# system_electric_diagram__3.net
KiCad netlist of a schematic drawn in Altium Designer
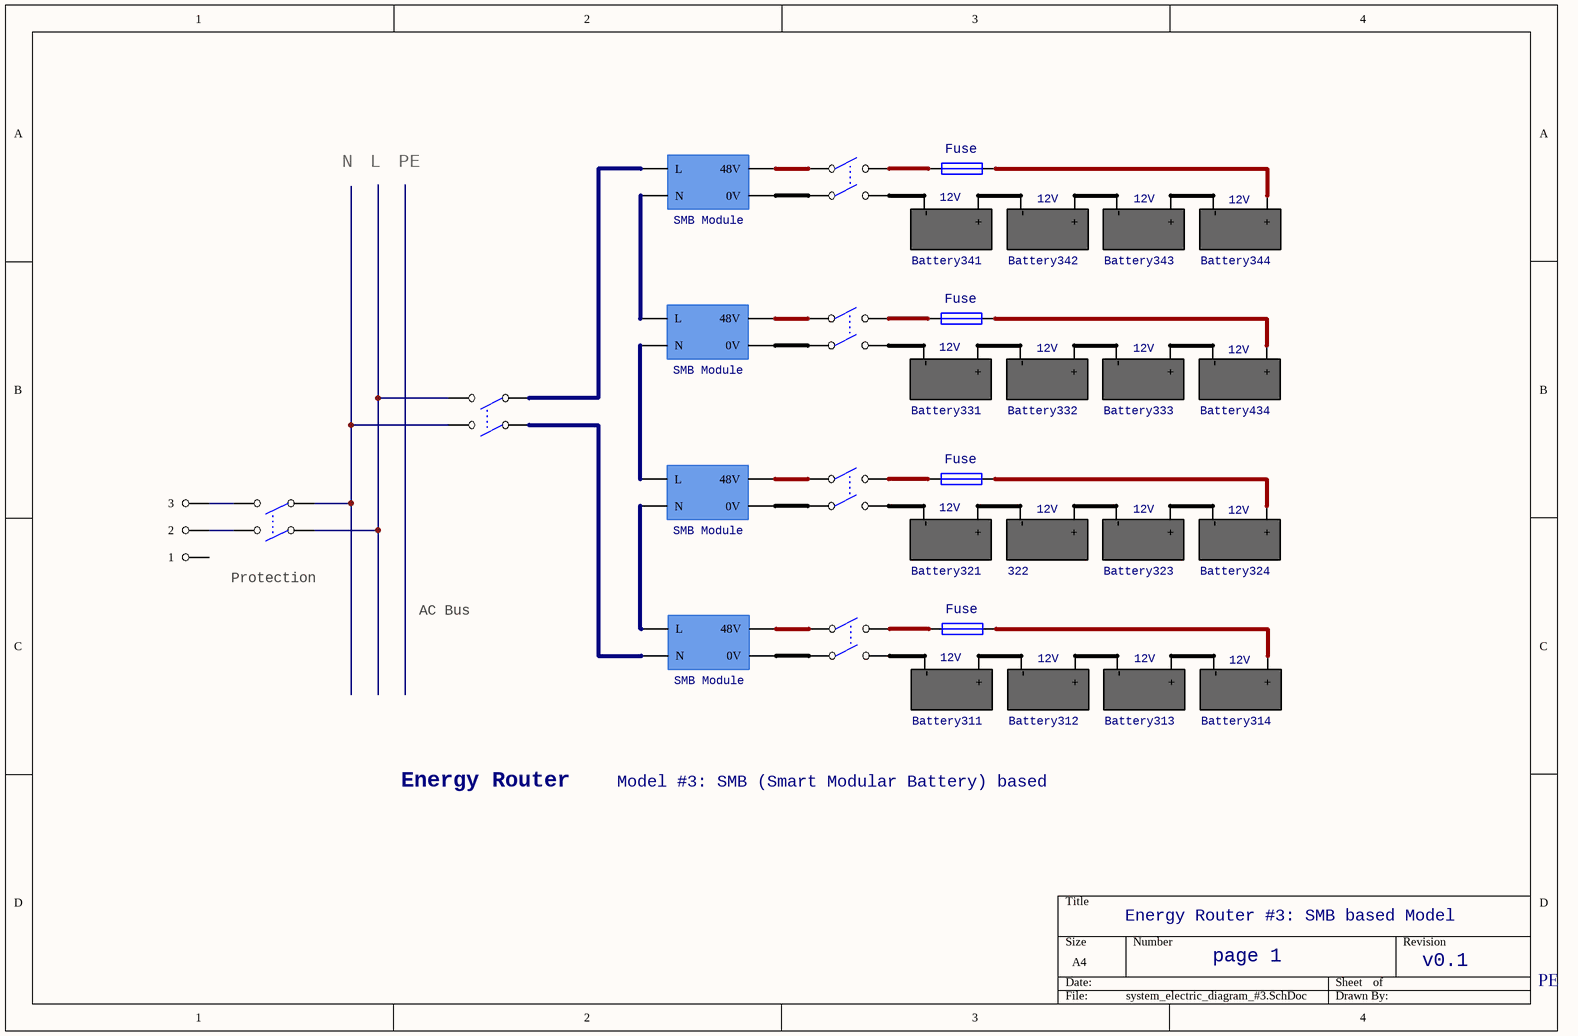
[diagram p0: system_electric_diagram_#3.SchDoc]

(export (version "E")
  (design (tool "Eeschema 10.0.6"))
  (components
    (comp (ref "322") (value "12V") (libsource (lib "0_Schlib-电源柜") (part "1_BAT_12V")))
    (comp (ref "Battery311") (value "12V") (libsource (lib "0_Schlib-电源柜") (part "1_BAT_12V")))
    (comp (ref "Battery312") (value "12V") (libsource (lib "0_Schlib-电源柜") (part "1_BAT_12V")))
    (comp (ref "Battery313") (value "12V") (libsource (lib "0_Schlib-电源柜") (part "1_BAT_12V")))
    (comp (ref "Battery314") (value "12V") (libsource (lib "0_Schlib-电源柜") (part "1_BAT_12V")))
    (comp (ref "Battery321") (value "12V") (libsource (lib "0_Schlib-电源柜") (part "1_BAT_12V")))
    (comp (ref "Battery323") (value "12V") (libsource (lib "0_Schlib-电源柜") (part "1_BAT_12V")))
    (comp (ref "Battery324") (value "12V") (libsource (lib "0_Schlib-电源柜") (part "1_BAT_12V")))
    (comp (ref "Battery331") (value "12V") (libsource (lib "0_Schlib-电源柜") (part "1_BAT_12V")))
    (comp (ref "Battery332") (value "12V") (libsource (lib "0_Schlib-电源柜") (part "1_BAT_12V")))
    (comp (ref "Battery333") (value "12V") (libsource (lib "0_Schlib-电源柜") (part "1_BAT_12V")))
    (comp (ref "Battery341") (value "12V") (libsource (lib "0_Schlib-电源柜") (part "1_BAT_12V")))
    (comp (ref "Battery342") (value "12V") (libsource (lib "0_Schlib-电源柜") (part "1_BAT_12V")))
    (comp (ref "Battery343") (value "12V") (libsource (lib "0_Schlib-电源柜") (part "1_BAT_12V")))
    (comp (ref "Battery344") (value "12V") (libsource (lib "0_Schlib-电源柜") (part "1_BAT_12V")))
    (comp (ref "Battery434") (value "12V") (libsource (lib "0_Schlib-电源柜") (part "1_BAT_12V")))
    (comp (ref "F301") (value "Fuse") (footprint "FUSE1") (libsource (lib "常用元件库") (part "FUSE")))
    (comp (ref "F302") (value "Fuse") (footprint "FUSE1") (libsource (lib "常用元件库") (part "FUSE")))
    (comp (ref "F303") (value "Fuse") (footprint "FUSE1") (libsource (lib "常用元件库") (part "FUSE")))
    (comp (ref "F304") (value "Fuse") (footprint "FUSE1") (libsource (lib "常用元件库") (part "FUSE")))
    (comp (ref "JP301")
      (value "3 HEADER")
      (description "3 Pin Header")
      (libsource (lib "myzou") (part "3 HEADER"))
    )
    (comp (ref "K301") (value "Switch") (libsource (lib "开关") (part "SW-DPST")))
    (comp (ref "K302") (value "Switch") (libsource (lib "开关") (part "SW-DPST")))
    (comp (ref "K303") (value "Switch") (libsource (lib "开关") (part "SW-DPST")))
    (comp (ref "K304") (value "Switch") (libsource (lib "开关") (part "SW-DPST")))
    (comp (ref "K305") (value "Switch") (libsource (lib "开关") (part "SW-DPST")))
    (comp (ref "K306") (value "Switch") (libsource (lib "开关") (part "SW-DPST")))
    (comp (ref "U301") (value "SMB Module") (libsource (lib "Schlib-ORES") (part "20_SMB_Module")))
    (comp (ref "U402") (value "SMB Module") (libsource (lib "Schlib-ORES") (part "20_SMB_Module")))
    (comp (ref "U403") (value "SMB Module") (libsource (lib "Schlib-ORES") (part "20_SMB_Module")))
    (comp (ref "U404") (value "SMB Module") (libsource (lib "Schlib-ORES") (part "20_SMB_Module")))
  )
  (nets
    (net (code "1") (name "Net-(322-+)") (class "Default")
      (node (ref "322") (pin "2") (pinfunction "+_2") (pintype "passive"))
      (node (ref "Battery323") (pin "1") (pinfunction "-_1") (pintype "passive"))
    )
    (net (code "2") (name "Net-(322--)") (class "Default")
      (node (ref "322") (pin "1") (pinfunction "-_1") (pintype "passive"))
      (node (ref "Battery321") (pin "2") (pinfunction "+_2") (pintype "passive"))
    )
    (net (code "3") (name "Net-(Battery311-+)") (class "Default")
      (node (ref "Battery311") (pin "2") (pinfunction "+_2") (pintype "passive"))
      (node (ref "Battery312") (pin "1") (pinfunction "-_1") (pintype "passive"))
    )
    (net (code "4") (name "Net-(Battery311--)") (class "Default")
      (node (ref "Battery311") (pin "1") (pinfunction "-_1") (pintype "passive"))
      (node (ref "K301") (pin "4") (pinfunction "4_4") (pintype "passive"))
    )
    (net (code "5") (name "Net-(Battery312-+)") (class "Default")
      (node (ref "Battery312") (pin "2") (pinfunction "+_2") (pintype "passive"))
      (node (ref "Battery313") (pin "1") (pinfunction "-_1") (pintype "passive"))
    )
    (net (code "6") (name "Net-(Battery313-+)") (class "Default")
      (node (ref "Battery313") (pin "2") (pinfunction "+_2") (pintype "passive"))
      (node (ref "Battery314") (pin "1") (pinfunction "-_1") (pintype "passive"))
    )
    (net (code "7") (name "Net-(Battery314-+)") (class "Default")
      (node (ref "Battery314") (pin "2") (pinfunction "+_2") (pintype "passive"))
      (node (ref "F301") (pin "2") (pinfunction "2_2") (pintype "passive"))
    )
    (net (code "8") (name "Net-(Battery321--)") (class "Default")
      (node (ref "Battery321") (pin "1") (pinfunction "-_1") (pintype "passive"))
      (node (ref "K302") (pin "4") (pinfunction "4_4") (pintype "passive"))
    )
    (net (code "9") (name "Net-(Battery323-+)") (class "Default")
      (node (ref "Battery323") (pin "2") (pinfunction "+_2") (pintype "passive"))
      (node (ref "Battery324") (pin "1") (pinfunction "-_1") (pintype "passive"))
    )
    (net (code "10") (name "Net-(Battery324-+)") (class "Default")
      (node (ref "Battery324") (pin "2") (pinfunction "+_2") (pintype "passive"))
      (node (ref "F302") (pin "2") (pinfunction "2_2") (pintype "passive"))
    )
    (net (code "11") (name "Net-(Battery331-+)") (class "Default")
      (node (ref "Battery331") (pin "2") (pinfunction "+_2") (pintype "passive"))
      (node (ref "Battery332") (pin "1") (pinfunction "-_1") (pintype "passive"))
    )
    (net (code "12") (name "Net-(Battery331--)") (class "Default")
      (node (ref "Battery331") (pin "1") (pinfunction "-_1") (pintype "passive"))
      (node (ref "K303") (pin "4") (pinfunction "4_4") (pintype "passive"))
    )
    (net (code "13") (name "Net-(Battery332-+)") (class "Default")
      (node (ref "Battery332") (pin "2") (pinfunction "+_2") (pintype "passive"))
      (node (ref "Battery333") (pin "1") (pinfunction "-_1") (pintype "passive"))
    )
    (net (code "14") (name "Net-(Battery333-+)") (class "Default")
      (node (ref "Battery333") (pin "2") (pinfunction "+_2") (pintype "passive"))
      (node (ref "Battery434") (pin "1") (pinfunction "-_1") (pintype "passive"))
    )
    (net (code "15") (name "Net-(Battery341-+)") (class "Default")
      (node (ref "Battery341") (pin "2") (pinfunction "+_2") (pintype "passive"))
      (node (ref "Battery342") (pin "1") (pinfunction "-_1") (pintype "passive"))
    )
    (net (code "16") (name "Net-(Battery341--)") (class "Default")
      (node (ref "Battery341") (pin "1") (pinfunction "-_1") (pintype "passive"))
      (node (ref "K304") (pin "4") (pinfunction "4_4") (pintype "passive"))
    )
    (net (code "17") (name "Net-(Battery342-+)") (class "Default")
      (node (ref "Battery342") (pin "2") (pinfunction "+_2") (pintype "passive"))
      (node (ref "Battery343") (pin "1") (pinfunction "-_1") (pintype "passive"))
    )
    (net (code "18") (name "Net-(Battery343-+)") (class "Default")
      (node (ref "Battery343") (pin "2") (pinfunction "+_2") (pintype "passive"))
      (node (ref "Battery344") (pin "1") (pinfunction "-_1") (pintype "passive"))
    )
    (net (code "19") (name "Net-(Battery344-+)") (class "Default")
      (node (ref "Battery344") (pin "2") (pinfunction "+_2") (pintype "passive"))
      (node (ref "F304") (pin "2") (pinfunction "2_2") (pintype "passive"))
    )
    (net (code "20") (name "Net-(Battery434-+)") (class "Default")
      (node (ref "Battery434") (pin "2") (pinfunction "+_2") (pintype "passive"))
      (node (ref "F303") (pin "2") (pinfunction "2_2") (pintype "passive"))
    )
    (net (code "21") (name "Net-(F301-Pad1)") (class "Default")
      (node (ref "F301") (pin "1") (pinfunction "1_1") (pintype "passive"))
      (node (ref "K301") (pin "2") (pinfunction "2_2") (pintype "passive"))
    )
    (net (code "22") (name "Net-(F302-Pad1)") (class "Default")
      (node (ref "F302") (pin "1") (pinfunction "1_1") (pintype "passive"))
      (node (ref "K302") (pin "2") (pinfunction "2_2") (pintype "passive"))
    )
    (net (code "23") (name "Net-(F303-Pad1)") (class "Default")
      (node (ref "F303") (pin "1") (pinfunction "1_1") (pintype "passive"))
      (node (ref "K303") (pin "2") (pinfunction "2_2") (pintype "passive"))
    )
    (net (code "24") (name "Net-(F304-Pad1)") (class "Default")
      (node (ref "F304") (pin "1") (pinfunction "1_1") (pintype "passive"))
      (node (ref "K304") (pin "2") (pinfunction "2_2") (pintype "passive"))
    )
    (net (code "25") (name "Net-(JP301-Pad2)") (class "Default")
      (node (ref "JP301") (pin "2") (pinfunction "2_2") (pintype "passive"))
      (node (ref "K306") (pin "2") (pinfunction "2_2") (pintype "passive"))
    )
    (net (code "26") (name "Net-(JP301-Pad3)") (class "Default")
      (node (ref "JP301") (pin "3") (pinfunction "3_3") (pintype "passive"))
      (node (ref "K306") (pin "4") (pinfunction "4_4") (pintype "passive"))
    )
    (net (code "27") (name "Net-(K305-Pad2)") (class "Default")
      (node (ref "K305") (pin "2") (pinfunction "2_2") (pintype "passive"))
      (node (ref "K306") (pin "3") (pinfunction "3_3") (pintype "passive"))
    )
    (net (code "28") (name "Net-(K305-Pad4)") (class "Default")
      (node (ref "K305") (pin "4") (pinfunction "4_4") (pintype "passive"))
      (node (ref "K306") (pin "1") (pinfunction "1_1") (pintype "passive"))
    )
    (net (code "29") (name "Net-(U301-0V)") (class "Default")
      (node (ref "K301") (pin "3") (pinfunction "3_3") (pintype "passive"))
      (node (ref "U301") (pin "4") (pinfunction "0V_4") (pintype "passive"))
    )
    (net (code "30") (name "Net-(U301-48V)") (class "Default")
      (node (ref "K301") (pin "1") (pinfunction "1_1") (pintype "passive"))
      (node (ref "U301") (pin "5") (pinfunction "48V_5") (pintype "passive"))
    )
    (net (code "31") (name "Net-(U301-L)") (class "Default")
      (node (ref "U301") (pin "2") (pinfunction "L_2") (pintype "passive"))
      (node (ref "U402") (pin "1") (pinfunction "N_1") (pintype "passive"))
    )
    (net (code "32") (name "Net-(U301-N)") (class "Default")
      (node (ref "K305") (pin "1") (pinfunction "1_1") (pintype "passive"))
      (node (ref "U301") (pin "1") (pinfunction "N_1") (pintype "passive"))
    )
    (net (code "33") (name "Net-(U402-0V)") (class "Default")
      (node (ref "K302") (pin "3") (pinfunction "3_3") (pintype "passive"))
      (node (ref "U402") (pin "4") (pinfunction "0V_4") (pintype "passive"))
    )
    (net (code "34") (name "Net-(U402-48V)") (class "Default")
      (node (ref "K302") (pin "1") (pinfunction "1_1") (pintype "passive"))
      (node (ref "U402") (pin "5") (pinfunction "48V_5") (pintype "passive"))
    )
    (net (code "35") (name "Net-(U402-L)") (class "Default")
      (node (ref "U402") (pin "2") (pinfunction "L_2") (pintype "passive"))
      (node (ref "U403") (pin "1") (pinfunction "N_1") (pintype "passive"))
    )
    (net (code "36") (name "Net-(U403-0V)") (class "Default")
      (node (ref "K303") (pin "3") (pinfunction "3_3") (pintype "passive"))
      (node (ref "U403") (pin "4") (pinfunction "0V_4") (pintype "passive"))
    )
    (net (code "37") (name "Net-(U403-48V)") (class "Default")
      (node (ref "K303") (pin "1") (pinfunction "1_1") (pintype "passive"))
      (node (ref "U403") (pin "5") (pinfunction "48V_5") (pintype "passive"))
    )
    (net (code "38") (name "Net-(U403-L)") (class "Default")
      (node (ref "U403") (pin "2") (pinfunction "L_2") (pintype "passive"))
      (node (ref "U404") (pin "1") (pinfunction "N_1") (pintype "passive"))
    )
    (net (code "39") (name "Net-(U404-0V)") (class "Default")
      (node (ref "K304") (pin "3") (pinfunction "3_3") (pintype "passive"))
      (node (ref "U404") (pin "4") (pinfunction "0V_4") (pintype "passive"))
    )
    (net (code "40") (name "Net-(U404-48V)") (class "Default")
      (node (ref "K304") (pin "1") (pinfunction "1_1") (pintype "passive"))
      (node (ref "U404") (pin "5") (pinfunction "48V_5") (pintype "passive"))
    )
    (net (code "41") (name "Net-(U404-L)") (class "Default")
      (node (ref "K305") (pin "3") (pinfunction "3_3") (pintype "passive"))
      (node (ref "U404") (pin "2") (pinfunction "L_2") (pintype "passive"))
    )
    (net (code "42") (name "unconnected-(JP301-Pad1)") (class "Default")
      (node (ref "JP301") (pin "1") (pinfunction "1_1") (pintype "passive"))
    )
  )
)
